# IF.net
KiCad netlist of a schematic drawn in Altium Designer
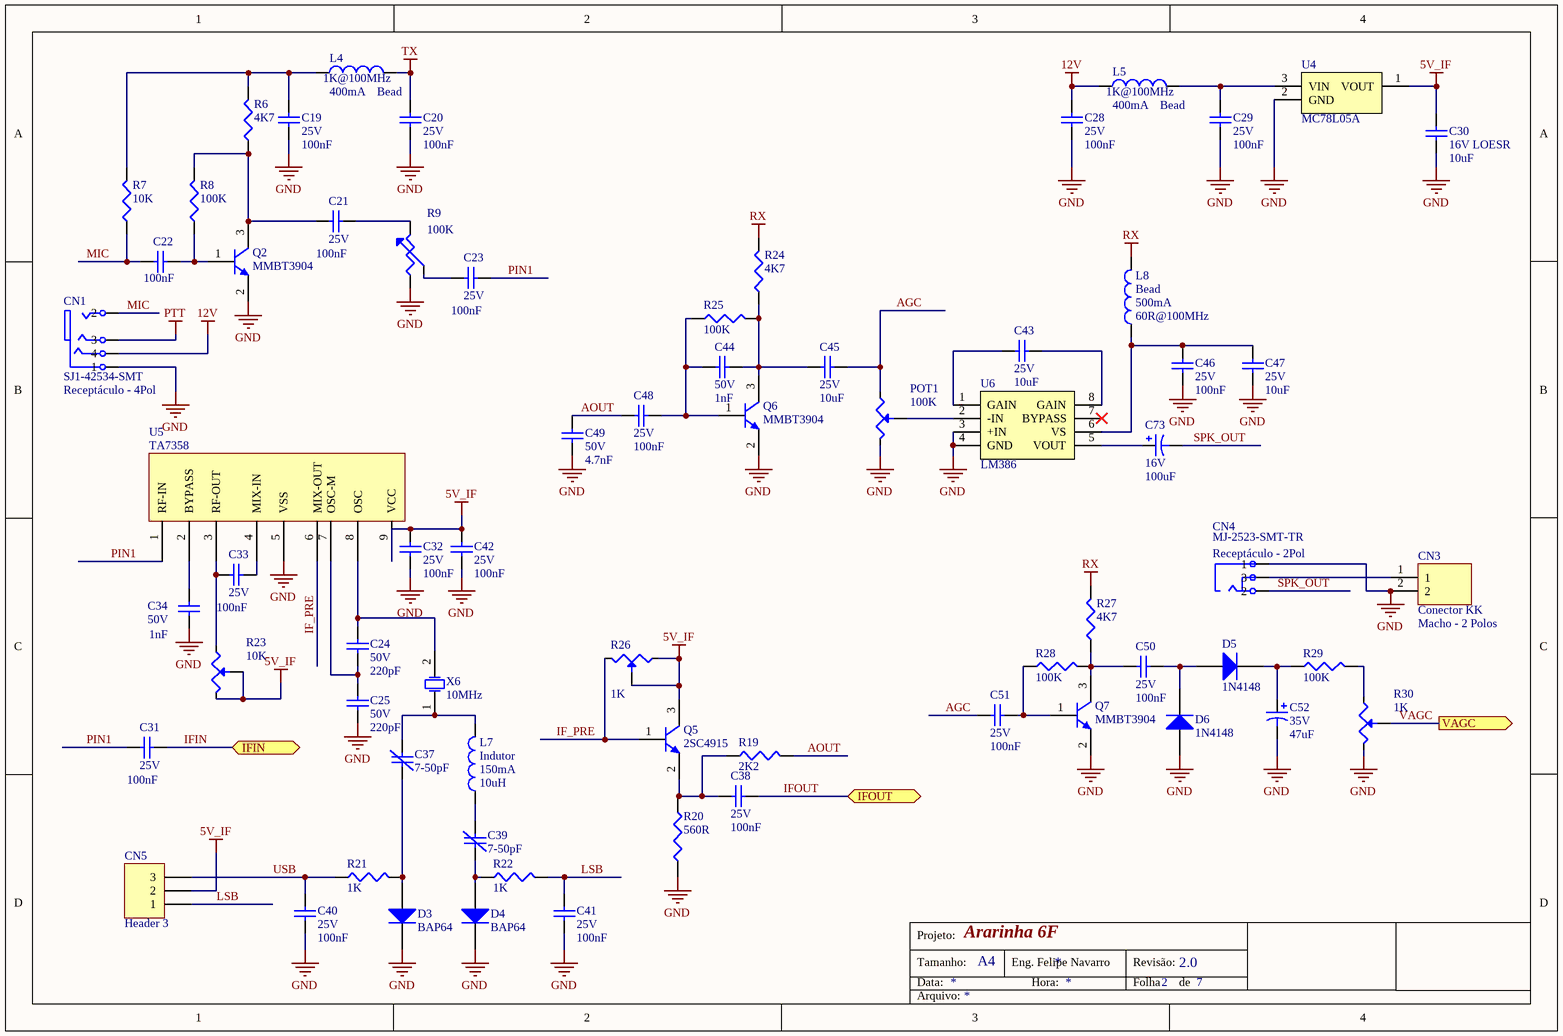
[diagram p0: IF.SchDoc]

(export (version "E")
  (design (tool "Eeschema 10.0.6"))
  (components
    (comp (ref "C19")
      (value "100nF")
      (footprint "CC0603")
      (description "Capacitor (Semiconductor SIM Model)")
      (fields (field (name "TENSÃO") "25V") (field (name "Comment") "Capacitor Cerâmico"))
      (libsource (lib "NavarroCAP") (part "Cap 100nF 25V 0603 X7R"))
    )
    (comp (ref "C20")
      (value "100nF")
      (footprint "CC0603")
      (description "Capacitor (Semiconductor SIM Model)")
      (fields (field (name "TENSÃO") "25V") (field (name "Comment") "Capacitor Cerâmico"))
      (libsource (lib "NavarroCAP") (part "Cap 100nF 25V 0603 X7R"))
    )
    (comp (ref "C21")
      (value "100nF")
      (footprint "CC0603")
      (description "Capacitor (Semiconductor SIM Model)")
      (fields (field (name "TENSÃO") "25V") (field (name "Comment") "Capacitor Cerâmico"))
      (libsource (lib "NavarroCAP") (part "Cap 100nF 25V 0603 X7R"))
    )
    (comp (ref "C22")
      (value "100nF")
      (footprint "CC0603")
      (description "Capacitor (Semiconductor SIM Model)")
      (fields (field (name "Comment") "Capacitor Cerâmico"))
      (libsource (lib "NavarroCAP") (part "Cap 100nF 25V 0603 X7R"))
    )
    (comp (ref "C23")
      (value "100nF")
      (footprint "CC0603")
      (description "Capacitor (Semiconductor SIM Model)")
      (fields (field (name "TENSÃO") "25V") (field (name "Comment") "Capacitor Cerâmico"))
      (libsource (lib "NavarroCAP") (part "Cap 100nF 25V 0603 X7R"))
    )
    (comp (ref "C24")
      (value "220pF")
      (footprint "CC0603")
      (description "Capacitor (Semiconductor SIM Model)")
      (fields (field (name "TENSÃO") "50V") (field (name "Comment") "Capacitor Cerâmico"))
      (libsource (lib "NavarroCAP") (part "Cap 220pF 50V 0603 NP0"))
    )
    (comp (ref "C25")
      (value "220pF")
      (footprint "CC0603")
      (description "Capacitor (Semiconductor SIM Model)")
      (fields (field (name "TENSÃO") "50V") (field (name "Comment") "Capacitor Cerâmico"))
      (libsource (lib "NavarroCAP") (part "Cap 220pF 50V 0603 NP0"))
    )
    (comp (ref "C28")
      (value "100nF")
      (footprint "CC0603")
      (description "Capacitor (Semiconductor SIM Model)")
      (fields (field (name "TENSÃO") "25V") (field (name "Comment") "Capacitor Cerâmico"))
      (libsource (lib "NavarroCAP") (part "Cap 100nF 25V 0603 X7R"))
    )
    (comp (ref "C29")
      (value "100nF")
      (footprint "CC0603")
      (description "Capacitor (Semiconductor SIM Model)")
      (fields (field (name "TENSÃO") "25V") (field (name "Comment") "Capacitor Cerâmico"))
      (libsource (lib "NavarroCAP") (part "Cap 100nF 25V 0603 X7R"))
    )
    (comp (ref "C30")
      (value "10uF")
      (footprint "CC0805")
      (description "Capacitor (Semiconductor SIM Model)")
      (fields (field (name "TENSÃO") "16V LOESR") (field (name "Comment") "Capacitor Cerâmico"))
      (libsource (lib "NavarroCAP") (part "Cap 10uF 16V 0805 X6S LOESR"))
    )
    (comp (ref "C31")
      (value "100nF")
      (footprint "CC0603")
      (description "Capacitor (Semiconductor SIM Model)")
      (fields (field (name "TENSÃO") "25V") (field (name "Comment") "Capacitor Cerâmico"))
      (libsource (lib "NavarroCAP") (part "Cap 100nF 25V 0603 X7R"))
    )
    (comp (ref "C32")
      (value "100nF")
      (footprint "CC0603")
      (description "Capacitor (Semiconductor SIM Model)")
      (fields (field (name "TENSÃO") "25V") (field (name "Comment") "Capacitor Cerâmico"))
      (libsource (lib "NavarroCAP") (part "Cap 100nF 25V 0603 X7R"))
    )
    (comp (ref "C33")
      (value "100nF")
      (footprint "CC0603")
      (description "Capacitor (Semiconductor SIM Model)")
      (fields (field (name "TENSÃO") "25V") (field (name "Comment") "Capacitor Cerâmico"))
      (libsource (lib "NavarroCAP") (part "Cap 100nF 25V 0603 X7R"))
    )
    (comp (ref "C34")
      (value "1nF")
      (footprint "CC0603")
      (description "Capacitor (Semiconductor SIM Model)")
      (fields (field (name "TENSÃO") "50V") (field (name "Comment") "Capacitor Cerâmico"))
      (libsource (lib "NavarroCAP") (part "Cap 1nF 50V 0603 NP0"))
    )
    (comp (ref "C37")
      (value "7-50pF")
      (footprint "MURATA TZB4")
      (description "Capacitor (Semiconductor SIM Model)")
      (fields (field (name "Comment") "Trimmer"))
      (libsource (lib "NavarroCAP") (part "Trimmer 7-50pF 50V TZB4-BB"))
    )
    (comp (ref "C38")
      (value "100nF")
      (footprint "CC0603")
      (description "Capacitor (Semiconductor SIM Model)")
      (fields (field (name "TENSÃO") "25V") (field (name "Comment") "Capacitor Cerâmico"))
      (libsource (lib "NavarroCAP") (part "Cap 100nF 25V 0603 X7R"))
    )
    (comp (ref "C39")
      (value "7-50pF")
      (footprint "MURATA TZB4")
      (description "Capacitor (Semiconductor SIM Model)")
      (fields (field (name "Comment") "Trimmer"))
      (libsource (lib "NavarroCAP") (part "Trimmer 7-50pF 50V TZB4-BB"))
    )
    (comp (ref "C40")
      (value "100nF")
      (footprint "CC0603")
      (description "Capacitor (Semiconductor SIM Model)")
      (fields (field (name "TENSÃO") "25V") (field (name "Comment") "Capacitor Cerâmico"))
      (libsource (lib "NavarroCAP") (part "Cap 100nF 25V 0603 X7R"))
    )
    (comp (ref "C41")
      (value "100nF")
      (footprint "CC0603")
      (description "Capacitor (Semiconductor SIM Model)")
      (fields (field (name "TENSÃO") "25V") (field (name "Comment") "Capacitor Cerâmico"))
      (libsource (lib "NavarroCAP") (part "Cap 100nF 25V 0603 X7R"))
    )
    (comp (ref "C42")
      (value "100nF")
      (footprint "CC0603")
      (description "Capacitor (Semiconductor SIM Model)")
      (fields (field (name "TENSÃO") "25V") (field (name "Comment") "Capacitor Cerâmico"))
      (libsource (lib "NavarroCAP") (part "Cap 100nF 25V 0603 X7R"))
    )
    (comp (ref "C43")
      (value "10uF")
      (footprint "CC0805")
      (description "Capacitor (Semiconductor SIM Model)")
      (fields (field (name "TENSÃO") "25V") (field (name "Comment") "Capacitor Cerâmico"))
      (libsource (lib "NavarroCAP") (part "Cap 10uF 25V 0805 X5R"))
    )
    (comp (ref "C44")
      (value "1nF")
      (footprint "CC0603")
      (description "Capacitor (Semiconductor SIM Model)")
      (fields (field (name "TENSÃO") "50V") (field (name "Comment") "Capacitor Cerâmico"))
      (libsource (lib "NavarroCAP") (part "Cap 1nF 50V 0603 NP0"))
    )
    (comp (ref "C45")
      (value "10uF")
      (footprint "CC0805")
      (description "Capacitor (Semiconductor SIM Model)")
      (fields (field (name "TENSÃO") "25V") (field (name "Comment") "Capacitor Cerâmico"))
      (libsource (lib "NavarroCAP") (part "Cap 10uF 25V 0805 X5R"))
    )
    (comp (ref "C46")
      (value "100nF")
      (footprint "CC0603")
      (description "Capacitor (Semiconductor SIM Model)")
      (fields (field (name "TENSÃO") "25V") (field (name "Comment") "Capacitor Cerâmico"))
      (libsource (lib "NavarroCAP") (part "Cap 100nF 25V 0603 X7R"))
    )
    (comp (ref "C47")
      (value "10uF")
      (footprint "CC0805")
      (description "Capacitor (Semiconductor SIM Model)")
      (fields (field (name "TENSÃO") "25V") (field (name "Comment") "Capacitor Cerâmico"))
      (libsource (lib "NavarroCAP") (part "Cap 10uF 25V 0805 X5R"))
    )
    (comp (ref "C48")
      (value "100nF")
      (footprint "CC0603")
      (description "Capacitor (Semiconductor SIM Model)")
      (fields (field (name "TENSÃO") "25V") (field (name "Comment") "Capacitor Cerâmico"))
      (libsource (lib "NavarroCAP") (part "Cap 100nF 25V 0603 X7R"))
    )
    (comp (ref "C49")
      (value "4.7nF")
      (footprint "CC0603")
      (description "Capacitor (Semiconductor SIM Model)")
      (fields (field (name "TENSÃO") "50V") (field (name "Comment") "Capacitor Cerâmico"))
      (libsource (lib "NavarroCAP") (part "Cap 4.7nF 50V 0603 X7R"))
    )
    (comp (ref "C50")
      (value "100nF")
      (footprint "CC0603")
      (description "Capacitor (Semiconductor SIM Model)")
      (fields (field (name "TENSÃO") "25V") (field (name "Comment") "Capacitor Cerâmico"))
      (libsource (lib "NavarroCAP") (part "Cap 100nF 25V 0603 X7R"))
    )
    (comp (ref "C51")
      (value "100nF")
      (footprint "CC0603")
      (description "Capacitor (Semiconductor SIM Model)")
      (fields (field (name "TENSÃO") "25V") (field (name "Comment") "Capacitor Cerâmico"))
      (libsource (lib "NavarroCAP") (part "Cap 100nF 25V 0603 X7R"))
    )
    (comp (ref "C52")
      (value "47uF")
      (footprint "CPOLRAD5X11")
      (description "Polarized Capacitor (Radial)")
      (fields (field (name "TENSÃO") "35V") (field (name "Comment") "Capacitor Eletrolítico"))
      (libsource (lib "NavarroCAP") (part "PCap 47uF 35V 5d.x11h."))
    )
    (comp (ref "C73")
      (value "100uF")
      (footprint "CPOLRAD6X12")
      (description "Polarized Capacitor (Radial)")
      (fields (field (name "TENSÃO") "16V") (field (name "Comment") "Capacitor Eletrolítico"))
      (libsource (lib "NavarroCAP") (part "PCap 100uF 16V 5d.x12h."))
    )
    (comp (ref "CN1")
      (value "SJ1-42534-SMT")
      (footprint "CONN_JACK-P2_2.5-4N")
      (description "Jack Socket, SMD Vertical, 4-Conductor Open Circuit")
      (fields (field (name "ALTIUM_VALUE") "Receptáculo - 4Pol"))
      (libsource (lib "NavarroCON") (part "Jack-4Pol"))
    )
    (comp (ref "CN3")
      (value "Conector KK")
      (footprint "CONN HDR2-POL P.100")
      (fields (field (name "ALTIUM_VALUE") "Macho - 2 Polos"))
      (libsource (lib "NavarroCON") (part "KK 2P Macho-V P2.54mm"))
    )
    (comp (ref "CN4")
      (value "MJ-2523-SMT-TR")
      (footprint "MJ-2523-SMT-TR")
      (description "CONN AUDIO JACK MONO 2.5MM SMD")
      (fields (field (name "ALTIUM_VALUE") "Receptáculo - 2Pol"))
      (libsource (lib "NavarroCON") (part "MJ-2523-SMT-TR"))
    )
    (comp (ref "CN5")
      (value "Header 3")
      (footprint "CONN HDR1X3")
      (description "Header, 3-Pin")
      (libsource (lib "NavarroCON") (part "Header 3"))
    )
    (comp (ref "D3")
      (value "BAP64")
      (footprint "SOD523")
      (description "PIN DIODE")
      (libsource (lib "NavarroSEMI") (part "PIN BAP64"))
    )
    (comp (ref "D4")
      (value "BAP64")
      (footprint "SOD523")
      (description "PIN DIODE")
      (libsource (lib "NavarroSEMI") (part "PIN BAP64"))
    )
    (comp (ref "D5")
      (value "1N4148")
      (footprint "SOD-323 Diodo-K2")
      (description "Small Signal Diodes")
      (libsource (lib "NavarroSEMI") (part "DP 75V 150mA SOD-323"))
    )
    (comp (ref "D6")
      (value "1N4148")
      (footprint "SOD-323 Diodo-K2")
      (description "Small Signal Diodes")
      (libsource (lib "NavarroSEMI") (part "DP 75V 150mA SOD-323"))
    )
    (comp (ref "L4")
      (value "Bead")
      (footprint "CC0603")
      (fields (field (name "CORRENTE") "400mA") (field (name "ALTIUM_VALUE") "1K@100MHz"))
      (libsource (lib "NavarroIND") (part "Bd 1K@100MHz 0603 400mA"))
    )
    (comp (ref "L5")
      (value "Bead")
      (footprint "CC0603")
      (fields (field (name "CORRENTE") "400mA") (field (name "ALTIUM_VALUE") "1K@100MHz"))
      (libsource (lib "NavarroIND") (part "Bd 1K@100MHz 0603 400mA"))
    )
    (comp (ref "L7")
      (value "Indutor")
      (footprint "CC0805")
      (description "Inductor")
      (fields (field (name "CORRENTE") "150mA") (field (name "ALTIUM_VALUE") "10uH"))
      (libsource (lib "NavarroIND") (part "Ind 10uH 0805 150mA"))
    )
    (comp (ref "L8")
      (value "Bead")
      (footprint "CC0603")
      (fields (field (name "CORRENTE") "500mA") (field (name "ALTIUM_VALUE") "60R@100MHz"))
      (libsource (lib "NavarroIND") (part "Bd 60R@100MHz 0603 500mA"))
    )
    (comp (ref "POT1")
      (value "100K")
      (footprint "POT - PTV09")
      (description "Potenciometro")
      (fields (field (name "Comment") "Potenciômetro"))
      (libsource (lib "NavarroRES") (part "POT 100k Audio"))
    )
    (comp (ref "Q2")
      (value "MMBT3904")
      (footprint "SOT-23-3N")
      (description "NPN General Purpose Amplifier")
      (libsource (lib "NavarroSEMI") (part "TRS MMBT3904 40V 200mA SOT-23-3N"))
    )
    (comp (ref "Q5")
      (value "2SC4915")
      (footprint "SOT-23-3N")
      (description "NPN General Purpose Amplifier")
      (libsource (lib "NavarroSEMI") (part "TRS 2SC3324 120V 100mA SOT-23-3"))
    )
    (comp (ref "Q6")
      (value "MMBT3904")
      (footprint "SOT-23-3N")
      (description "NPN General Purpose Amplifier")
      (libsource (lib "NavarroSEMI") (part "TRS MMBT3904 40V 200mA SOT-23-3N"))
    )
    (comp (ref "Q7")
      (value "MMBT3904")
      (footprint "SOT-23-3N")
      (description "NPN General Purpose Amplifier")
      (libsource (lib "NavarroSEMI") (part "TRS MMBT2222 40V 200mA SOT-23-3N"))
    )
    (comp (ref "R6")
      (value "4K7")
      (footprint "CC0603")
      (description "Resistor")
      (libsource (lib "NavarroRES") (part "Res 4K7 1% 0603 1/10W"))
    )
    (comp (ref "R7")
      (value "10K")
      (footprint "CC0603")
      (description "Resistor")
      (libsource (lib "NavarroRES") (part "Res 10K 1% 0603 1/10W"))
    )
    (comp (ref "R8")
      (value "100K")
      (footprint "CC0603")
      (description "Resistor")
      (libsource (lib "NavarroRES") (part "Res 100K 1% 0603 1/10W"))
    )
    (comp (ref "R9")
      (value "100K")
      (footprint "POT")
      (description "Trimmer")
      (fields (field (name "Comment") "Potenciômetro"))
      (libsource (lib "NavarroRES") (part "Res Trim"))
    )
    (comp (ref "R19")
      (value "2K2")
      (footprint "CC0603")
      (description "Resistor")
      (libsource (lib "NavarroRES") (part "Res 2K2 5% 0603 1/10W"))
    )
    (comp (ref "R20")
      (value "560R")
      (footprint "CC0603")
      (description "Resistor")
      (libsource (lib "NavarroRES") (part "Res 560R 1% 0603 1/10w"))
    )
    (comp (ref "R21")
      (value "1K")
      (footprint "CC0603")
      (description "Resistor")
      (libsource (lib "NavarroRES") (part "Res 1K 1% 0603 1/10W"))
    )
    (comp (ref "R22")
      (value "1K")
      (footprint "CC0603")
      (description "Resistor")
      (libsource (lib "NavarroRES") (part "Res 1K 1% 0603 1/10W"))
    )
    (comp (ref "R23")
      (value "10K")
      (footprint "POT")
      (description "Potenciometro")
      (fields (field (name "Comment") "Potenciômetro"))
      (libsource (lib "NavarroRES") (part "Res Pot"))
    )
    (comp (ref "R24")
      (value "4K7")
      (footprint "CC0603")
      (description "Resistor")
      (libsource (lib "NavarroRES") (part "Res 4K7 1% 0603 1/10W"))
    )
    (comp (ref "R25")
      (value "100K")
      (footprint "CC0603")
      (description "Resistor")
      (libsource (lib "NavarroRES") (part "Res 100K 1% 0603 1/10W"))
    )
    (comp (ref "R26")
      (value "1K")
      (footprint "POT")
      (description "Potenciometro")
      (fields (field (name "Comment") "Potenciômetro"))
      (libsource (lib "NavarroRES") (part "Res Pot"))
    )
    (comp (ref "R27")
      (value "4K7")
      (footprint "CC0603")
      (description "Resistor")
      (libsource (lib "NavarroRES") (part "Res 4K7 1% 0603 1/10W"))
    )
    (comp (ref "R28")
      (value "100K")
      (footprint "CC0603")
      (description "Resistor")
      (libsource (lib "NavarroRES") (part "Res 100K 1% 0603 1/10W"))
    )
    (comp (ref "R29")
      (value "100K")
      (footprint "CC0603")
      (description "Resistor")
      (libsource (lib "NavarroRES") (part "Res 100K 1% 0603 1/10W"))
    )
    (comp (ref "R30")
      (value "1K")
      (footprint "POT")
      (description "Potenciometro")
      (fields (field (name "Comment") "Potenciômetro"))
      (libsource (lib "NavarroRES") (part "Res Pot"))
    )
    (comp (ref "U4")
      (value "MC78L05A")
      (footprint "SOT-89-3N")
      (description "Regulador Linear 5V")
      (libsource (lib "Navarro") (part "MC78L05"))
    )
    (comp (ref "U5")
      (value "TA7358")
      (footprint "SIP9")
      (description "FM FRONT-END")
      (libsource (lib "Navarro") (part "TA7358"))
    )
    (comp (ref "U6")
      (value "LM386")
      (footprint "SOIC-8N")
      (description "IC AMP AUDIO PWR .325W AB 8SOIC")
      (libsource (lib "Navarro") (part "LM386"))
    )
    (comp (ref "X6")
      (value "10MHz")
      (footprint "HC/49US")
      (description "Crystal Oscillator")
      (libsource (lib "Navarro") (part "XTAL"))
    )
  )
  (nets
    (net (code "1") (name "/AGC") (class "Default")
      (node (ref "C45") (pin "2") (pinfunction "2_2") (pintype "passive"))
      (node (ref "C51") (pin "1") (pinfunction "1_1") (pintype "passive"))
      (node (ref "POT1") (pin "1") (pinfunction "1_1") (pintype "passive"))
    )
    (net (code "2") (name "/AOUT") (class "Default")
      (node (ref "C48") (pin "1") (pinfunction "1_1") (pintype "passive"))
      (node (ref "C49") (pin "2") (pinfunction "2_2") (pintype "passive"))
      (node (ref "R19") (pin "2") (pinfunction "2_2") (pintype "passive"))
    )
    (net (code "3") (name "/IFIN") (class "Default")
      (node (ref "C31") (pin "1") (pinfunction "1_1") (pintype "passive"))
    )
    (net (code "4") (name "/IFOUT") (class "Default")
      (node (ref "C38") (pin "2") (pinfunction "2_2") (pintype "passive"))
    )
    (net (code "5") (name "/IF_PRE") (class "Default")
      (node (ref "Q5") (pin "1") (pinfunction "B_1") (pintype "passive"))
      (node (ref "R26") (pin "3") (pinfunction "3_3") (pintype "passive"))
      (node (ref "U5") (pin "6") (pinfunction "MIX-OUT_6") (pintype "passive"))
    )
    (net (code "6") (name "/LSB") (class "Default")
      (node (ref "C41") (pin "1") (pinfunction "1_1") (pintype "passive"))
      (node (ref "CN5") (pin "1") (pinfunction "1_1") (pintype "passive"))
      (node (ref "R22") (pin "2") (pinfunction "2_2") (pintype "passive"))
    )
    (net (code "7") (name "/MIC") (class "Default")
      (node (ref "C22") (pin "2") (pinfunction "2_2") (pintype "passive"))
      (node (ref "CN1") (pin "2") (pinfunction "2_2") (pintype "power_in"))
      (node (ref "R7") (pin "1") (pinfunction "1_1") (pintype "passive"))
    )
    (net (code "8") (name "/PIN1") (class "Default")
      (node (ref "C23") (pin "1") (pinfunction "1_1") (pintype "passive"))
      (node (ref "C31") (pin "2") (pinfunction "2_2") (pintype "passive"))
      (node (ref "U5") (pin "1") (pinfunction "RF-IN_1") (pintype "passive"))
    )
    (net (code "9") (name "/SPK_OUT") (class "Default")
      (node (ref "C73") (pin "2") (pinfunction "2_2") (pintype "passive"))
      (node (ref "CN4") (pin "2") (pinfunction "2_2") (pintype "power_in"))
    )
    (net (code "10") (name "/USB") (class "Default")
      (node (ref "C40") (pin "1") (pinfunction "1_1") (pintype "passive"))
      (node (ref "CN5") (pin "3") (pinfunction "3_3") (pintype "passive"))
      (node (ref "R21") (pin "1") (pinfunction "1_1") (pintype "passive"))
    )
    (net (code "11") (name "/VAGC") (class "Default")
      (node (ref "R30") (pin "2") (pinfunction "TAP_2") (pintype "passive"))
    )
    (net (code "12") (name "5V_IF") (class "Default")
      (node (ref "C30") (pin "2") (pinfunction "2_2") (pintype "passive"))
      (node (ref "C32") (pin "1") (pinfunction "1_1") (pintype "passive"))
      (node (ref "C42") (pin "1") (pinfunction "1_1") (pintype "passive"))
      (node (ref "CN5") (pin "2") (pinfunction "2_2") (pintype "passive"))
      (node (ref "Q5") (pin "3") (pinfunction "C_3") (pintype "passive"))
      (node (ref "R23") (pin "2") (pinfunction "TAP_2") (pintype "passive"))
      (node (ref "R23") (pin "3") (pinfunction "3_3") (pintype "passive"))
      (node (ref "R26") (pin "1") (pinfunction "1_1") (pintype "passive"))
      (node (ref "R26") (pin "2") (pinfunction "TAP_2") (pintype "passive"))
      (node (ref "U4") (pin "1") (pinfunction "VOUT_1") (pintype "power_in"))
      (node (ref "U5") (pin "9") (pinfunction "VCC_9") (pintype "passive"))
    )
    (net (code "13") (name "12V") (class "Default")
      (node (ref "C28") (pin "1") (pinfunction "1_1") (pintype "passive"))
      (node (ref "CN1") (pin "4") (pinfunction "4_4") (pintype "power_in"))
      (node (ref "L5") (pin "1") (pinfunction "1_1") (pintype "passive"))
    )
    (net (code "14") (name "GND") (class "Default")
      (node (ref "C19") (pin "2") (pinfunction "2_2") (pintype "passive"))
      (node (ref "C20") (pin "2") (pinfunction "2_2") (pintype "passive"))
      (node (ref "C25") (pin "1") (pinfunction "1_1") (pintype "passive"))
      (node (ref "C28") (pin "2") (pinfunction "2_2") (pintype "passive"))
      (node (ref "C29") (pin "2") (pinfunction "2_2") (pintype "passive"))
      (node (ref "C30") (pin "1") (pinfunction "1_1") (pintype "passive"))
      (node (ref "C32") (pin "2") (pinfunction "2_2") (pintype "passive"))
      (node (ref "C34") (pin "2") (pinfunction "2_2") (pintype "passive"))
      (node (ref "C40") (pin "2") (pinfunction "2_2") (pintype "passive"))
      (node (ref "C41") (pin "2") (pinfunction "2_2") (pintype "passive"))
      (node (ref "C42") (pin "2") (pinfunction "2_2") (pintype "passive"))
      (node (ref "C46") (pin "2") (pinfunction "2_2") (pintype "passive"))
      (node (ref "C47") (pin "1") (pinfunction "1_1") (pintype "passive"))
      (node (ref "C49") (pin "1") (pinfunction "1_1") (pintype "passive"))
      (node (ref "C52") (pin "2") (pinfunction "2_2") (pintype "passive"))
      (node (ref "CN1") (pin "1") (pinfunction "1_1") (pintype "passive"))
      (node (ref "CN3") (pin "2") (pinfunction "2_2") (pintype "passive"))
      (node (ref "CN4") (pin "1") (pinfunction "1_1") (pintype "passive"))
      (node (ref "D3") (pin "2") (pinfunction "K_2") (pintype "passive"))
      (node (ref "D4") (pin "2") (pinfunction "K_2") (pintype "passive"))
      (node (ref "D6") (pin "1") (pinfunction "A_1") (pintype "passive"))
      (node (ref "POT1") (pin "3") (pinfunction "3_3") (pintype "passive"))
      (node (ref "Q2") (pin "2") (pinfunction "E_2") (pintype "passive"))
      (node (ref "Q6") (pin "2") (pinfunction "E_2") (pintype "passive"))
      (node (ref "Q7") (pin "2") (pinfunction "E_2") (pintype "passive"))
      (node (ref "R20") (pin "1") (pinfunction "1_1") (pintype "passive"))
      (node (ref "R30") (pin "3") (pinfunction "3_3") (pintype "passive"))
      (node (ref "R9") (pin "2") (pinfunction "2_2") (pintype "passive"))
      (node (ref "U4") (pin "2") (pinfunction "GND_2") (pintype "power_in"))
      (node (ref "U5") (pin "5") (pinfunction "VSS_5") (pintype "passive"))
      (node (ref "U6") (pin "3") (pinfunction "+IN_3") (pintype "passive"))
      (node (ref "U6") (pin "4") (pinfunction "GND_4") (pintype "passive"))
    )
    (net (code "15") (name "Net-(C19-Pad1)") (class "Default")
      (node (ref "C19") (pin "1") (pinfunction "1_1") (pintype "passive"))
      (node (ref "L4") (pin "1") (pinfunction "1_1") (pintype "passive"))
      (node (ref "R6") (pin "2") (pinfunction "2_2") (pintype "passive"))
      (node (ref "R7") (pin "2") (pinfunction "2_2") (pintype "passive"))
    )
    (net (code "16") (name "Net-(C21-Pad1)") (class "Default")
      (node (ref "C21") (pin "1") (pinfunction "1_1") (pintype "passive"))
      (node (ref "R9") (pin "1") (pinfunction "1_1") (pintype "passive"))
    )
    (net (code "17") (name "Net-(C39-Pad2)") (class "Default")
      (node (ref "C39") (pin "2") (pinfunction "2_2") (pintype "passive"))
      (node (ref "L7") (pin "1") (pinfunction "1_1") (pintype "passive"))
    )
    (net (code "18") (name "Net-(C43-Pad1)") (class "Default")
      (node (ref "C43") (pin "1") (pinfunction "1_1") (pintype "passive"))
      (node (ref "U6") (pin "1") (pinfunction "GAIN_1") (pintype "passive"))
    )
    (net (code "19") (name "Net-(C43-Pad2)") (class "Default")
      (node (ref "C43") (pin "2") (pinfunction "2_2") (pintype "passive"))
      (node (ref "U6") (pin "8") (pinfunction "GAIN_8") (pintype "passive"))
    )
    (net (code "20") (name "Net-(CN3-Pad1)") (class "Default")
      (node (ref "CN3") (pin "1") (pinfunction "1_1") (pintype "passive"))
      (node (ref "CN4") (pin "3") (pinfunction "3_3") (pintype "power_in"))
    )
    (net (code "21") (name "Net-(D3-A)") (class "Default")
      (node (ref "C37") (pin "1") (pinfunction "1_1") (pintype "passive"))
      (node (ref "D3") (pin "1") (pinfunction "A_1") (pintype "passive"))
      (node (ref "R21") (pin "2") (pinfunction "2_2") (pintype "passive"))
    )
    (net (code "22") (name "Net-(D4-A)") (class "Default")
      (node (ref "C39") (pin "1") (pinfunction "1_1") (pintype "passive"))
      (node (ref "D4") (pin "1") (pinfunction "A_1") (pintype "passive"))
      (node (ref "R22") (pin "1") (pinfunction "1_1") (pintype "passive"))
    )
    (net (code "23") (name "Net-(D5-A)") (class "Default")
      (node (ref "C50") (pin "2") (pinfunction "2_2") (pintype "passive"))
      (node (ref "D5") (pin "1") (pinfunction "A_1") (pintype "passive"))
      (node (ref "D6") (pin "2") (pinfunction "K_2") (pintype "passive"))
    )
    (net (code "24") (name "Net-(D5-K)") (class "Default")
      (node (ref "C52") (pin "1") (pinfunction "1_1") (pintype "passive"))
      (node (ref "D5") (pin "2") (pinfunction "K_2") (pintype "passive"))
      (node (ref "R29") (pin "1") (pinfunction "1_1") (pintype "passive"))
    )
    (net (code "25") (name "Net-(POT1-TAP)") (class "Default")
      (node (ref "POT1") (pin "2") (pinfunction "TAP_2") (pintype "passive"))
      (node (ref "U6") (pin "2") (pinfunction "-IN_2") (pintype "passive"))
    )
    (net (code "26") (name "Net-(Q2-B)") (class "Default")
      (node (ref "C22") (pin "1") (pinfunction "1_1") (pintype "passive"))
      (node (ref "Q2") (pin "1") (pinfunction "B_1") (pintype "passive"))
      (node (ref "R8") (pin "1") (pinfunction "1_1") (pintype "passive"))
    )
    (net (code "27") (name "Net-(Q2-C)") (class "Default")
      (node (ref "C21") (pin "2") (pinfunction "2_2") (pintype "passive"))
      (node (ref "Q2") (pin "3") (pinfunction "C_3") (pintype "passive"))
      (node (ref "R6") (pin "1") (pinfunction "1_1") (pintype "passive"))
      (node (ref "R8") (pin "2") (pinfunction "2_2") (pintype "passive"))
    )
    (net (code "28") (name "Net-(Q5-E)") (class "Default")
      (node (ref "C38") (pin "1") (pinfunction "1_1") (pintype "passive"))
      (node (ref "Q5") (pin "2") (pinfunction "E_2") (pintype "passive"))
      (node (ref "R19") (pin "1") (pinfunction "1_1") (pintype "passive"))
      (node (ref "R20") (pin "2") (pinfunction "2_2") (pintype "passive"))
    )
    (net (code "29") (name "Net-(Q6-B)") (class "Default")
      (node (ref "C44") (pin "1") (pinfunction "1_1") (pintype "passive"))
      (node (ref "C48") (pin "2") (pinfunction "2_2") (pintype "passive"))
      (node (ref "Q6") (pin "1") (pinfunction "B_1") (pintype "passive"))
      (node (ref "R25") (pin "1") (pinfunction "1_1") (pintype "passive"))
    )
    (net (code "30") (name "Net-(Q6-C)") (class "Default")
      (node (ref "C44") (pin "2") (pinfunction "2_2") (pintype "passive"))
      (node (ref "C45") (pin "1") (pinfunction "1_1") (pintype "passive"))
      (node (ref "Q6") (pin "3") (pinfunction "C_3") (pintype "passive"))
      (node (ref "R24") (pin "1") (pinfunction "1_1") (pintype "passive"))
      (node (ref "R25") (pin "2") (pinfunction "2_2") (pintype "passive"))
    )
    (net (code "31") (name "Net-(Q7-B)") (class "Default")
      (node (ref "C51") (pin "2") (pinfunction "2_2") (pintype "passive"))
      (node (ref "Q7") (pin "1") (pinfunction "B_1") (pintype "passive"))
      (node (ref "R28") (pin "1") (pinfunction "1_1") (pintype "passive"))
    )
    (net (code "32") (name "Net-(Q7-C)") (class "Default")
      (node (ref "C50") (pin "1") (pinfunction "1_1") (pintype "passive"))
      (node (ref "Q7") (pin "3") (pinfunction "C_3") (pintype "passive"))
      (node (ref "R27") (pin "1") (pinfunction "1_1") (pintype "passive"))
      (node (ref "R28") (pin "2") (pinfunction "2_2") (pintype "passive"))
    )
    (net (code "33") (name "Net-(R9-TAP)") (class "Default")
      (node (ref "C23") (pin "2") (pinfunction "2_2") (pintype "passive"))
      (node (ref "R9") (pin "3") (pinfunction "TAP_3") (pintype "passive"))
    )
    (net (code "34") (name "Net-(R29-Pad2)") (class "Default")
      (node (ref "R29") (pin "2") (pinfunction "2_2") (pintype "passive"))
      (node (ref "R30") (pin "1") (pinfunction "1_1") (pintype "passive"))
    )
    (net (code "35") (name "Net-(U4-VIN)") (class "Default")
      (node (ref "C29") (pin "1") (pinfunction "1_1") (pintype "passive"))
      (node (ref "L5") (pin "2") (pinfunction "2_2") (pintype "passive"))
      (node (ref "U4") (pin "3") (pinfunction "VIN_3") (pintype "power_in"))
    )
    (net (code "36") (name "Net-(U5-BYPASS)") (class "Default")
      (node (ref "C34") (pin "1") (pinfunction "1_1") (pintype "passive"))
      (node (ref "U5") (pin "2") (pinfunction "BYPASS_2") (pintype "passive"))
    )
    (net (code "37") (name "Net-(U5-MIX-IN)") (class "Default")
      (node (ref "C33") (pin "1") (pinfunction "1_1") (pintype "passive"))
      (node (ref "U5") (pin "4") (pinfunction "MIX-IN_4") (pintype "passive"))
    )
    (net (code "38") (name "Net-(U5-OSC)") (class "Default")
      (node (ref "C24") (pin "2") (pinfunction "2_2") (pintype "passive"))
      (node (ref "U5") (pin "8") (pinfunction "OSC_8") (pintype "passive"))
      (node (ref "X6") (pin "2") (pinfunction "OSC2_2") (pintype "passive"))
    )
    (net (code "39") (name "Net-(U5-OSC-M)") (class "Default")
      (node (ref "C24") (pin "1") (pinfunction "1_1") (pintype "passive"))
      (node (ref "C25") (pin "2") (pinfunction "2_2") (pintype "passive"))
      (node (ref "U5") (pin "7") (pinfunction "OSC-M_7") (pintype "passive"))
    )
    (net (code "40") (name "Net-(U5-RF-OUT)") (class "Default")
      (node (ref "C33") (pin "2") (pinfunction "2_2") (pintype "passive"))
      (node (ref "R23") (pin "1") (pinfunction "1_1") (pintype "passive"))
      (node (ref "U5") (pin "3") (pinfunction "RF-OUT_3") (pintype "passive"))
    )
    (net (code "41") (name "Net-(U6-VOUT)") (class "Default")
      (node (ref "C73") (pin "1") (pinfunction "1_1") (pintype "passive"))
      (node (ref "U6") (pin "5") (pinfunction "VOUT_5") (pintype "passive"))
    )
    (net (code "42") (name "Net-(U6-VS)") (class "Default")
      (node (ref "C46") (pin "1") (pinfunction "1_1") (pintype "passive"))
      (node (ref "C47") (pin "2") (pinfunction "2_2") (pintype "passive"))
      (node (ref "L8") (pin "1") (pinfunction "1_1") (pintype "passive"))
      (node (ref "U6") (pin "6") (pinfunction "VS_6") (pintype "passive"))
    )
    (net (code "43") (name "Net-(X6-OSC1)") (class "Default")
      (node (ref "C37") (pin "2") (pinfunction "2_2") (pintype "passive"))
      (node (ref "L7") (pin "2") (pinfunction "2_2") (pintype "passive"))
      (node (ref "X6") (pin "1") (pinfunction "OSC1_1") (pintype "passive"))
    )
    (net (code "44") (name "PTT") (class "Default")
      (node (ref "CN1") (pin "3") (pinfunction "3_3") (pintype "power_in"))
    )
    (net (code "45") (name "RX") (class "Default")
      (node (ref "L8") (pin "2") (pinfunction "2_2") (pintype "passive"))
      (node (ref "R24") (pin "2") (pinfunction "2_2") (pintype "passive"))
      (node (ref "R27") (pin "2") (pinfunction "2_2") (pintype "passive"))
    )
    (net (code "46") (name "TX") (class "Default")
      (node (ref "C20") (pin "1") (pinfunction "1_1") (pintype "passive"))
      (node (ref "L4") (pin "2") (pinfunction "2_2") (pintype "passive"))
    )
    (net (code "47") (name "unconnected-(U6-BYPASS-Pad7)") (class "Default")
      (node (ref "U6") (pin "7") (pinfunction "BYPASS_7") (pintype "passive+no_connect"))
    )
  )
)
